# Main.net
KiCad netlist of a schematic drawn in Altium Designer
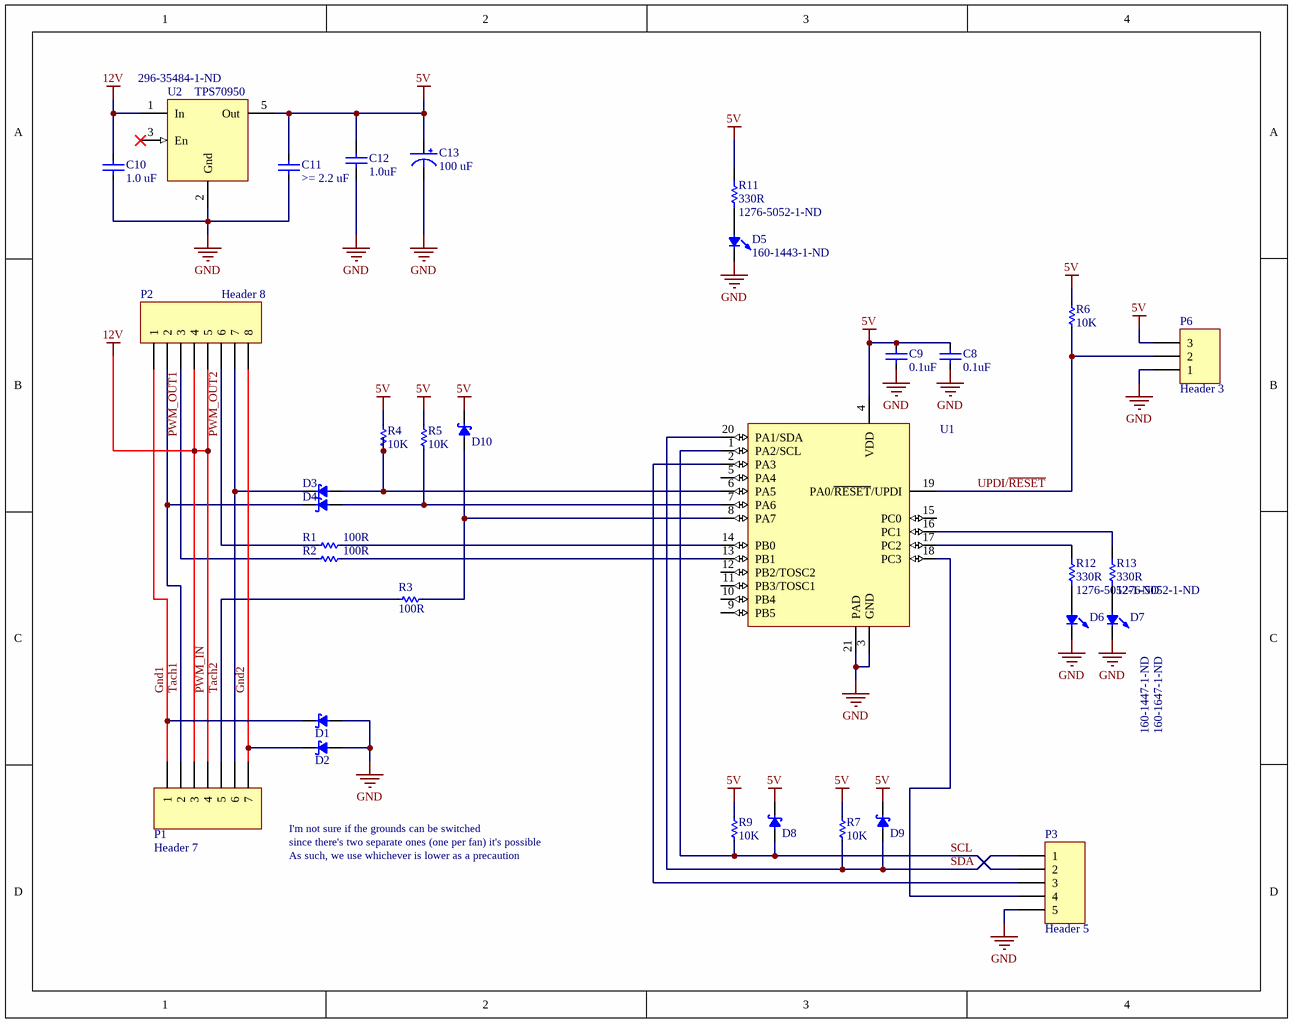
[diagram p0: Main.SchDoc]

(export (version "E")
  (design (tool "Eeschema 10.0.6"))
  (components
    (comp (ref "C8")
      (value "0.1uF")
      (footprint "0603C")
      (description "Capacitor")
      (fields (field (name "Comment") "Cap"))
      (libsource (lib "Miscellaneous Devices") (part "Cap"))
    )
    (comp (ref "C9")
      (value "0.1uF")
      (footprint "0603C")
      (description "Capacitor")
      (fields (field (name "Comment") "Cap"))
      (libsource (lib "Miscellaneous Devices") (part "Cap"))
    )
    (comp (ref "C10")
      (value "1.0 uF")
      (footprint "1206C")
      (description "Capacitor")
      (fields (field (name "Comment") "Cap") (field (name "PUBLISHER") "Altium Limited"))
      (libsource (lib "Miscellaneous Devices") (part "Cap"))
    )
    (comp (ref "C11")
      (value ">= 2.2 uF")
      (footprint "1206C")
      (description "Capacitor")
      (fields (field (name "Comment") "Cap") (field (name "PUBLISHER") "Altium Limited"))
      (libsource (lib "Miscellaneous Devices") (part "Cap"))
    )
    (comp (ref "C12")
      (value "1.0uF")
      (footprint "1206C")
      (description "Capacitor (Semiconductor SIM Model)")
      (fields (field (name "Comment") "Cap Semi") (field (name "PUBLISHER") "Altium Limited"))
      (libsource (lib "Miscellaneous Devices") (part "Cap Semi"))
    )
    (comp (ref "C13")
      (value "100 uF")
      (footprint "B")
      (libsource (lib "DAQ Sstem") (part "100 uf SMT Panasonic Cap"))
    )
    (comp (ref "D1")
      (value "Schottky Diode")
      (footprint "SOD-323")
      (libsource (lib "Unsorted") (part "Schottky Diode"))
    )
    (comp (ref "D2")
      (value "Schottky Diode")
      (footprint "SOD-323")
      (libsource (lib "Unsorted") (part "Schottky Diode"))
    )
    (comp (ref "D3")
      (value "Schottky Diode")
      (footprint "SOD-323")
      (libsource (lib "Unsorted") (part "Schottky Diode"))
    )
    (comp (ref "D4")
      (value "Schottky Diode")
      (footprint "SOD-323")
      (libsource (lib "Unsorted") (part "Schottky Diode"))
    )
    (comp (ref "D5")
      (value "LED0")
      (footprint "0603 SMT LED")
      (description "T 1 3/4 LED")
      (fields
        (field (name "SUPPLIER PART NUMBER 1") "160-1443-1-ND")
        (field (name "PUBLISHER") "Altium Limited")
      )
      (libsource (lib "Miscellaneous Devices") (part "LED0"))
    )
    (comp (ref "D6")
      (value "LED0")
      (footprint "0603 SMT LED")
      (description "T 1 3/4 LED")
      (fields
        (field (name "SUPPLIER PART NUMBER 1") "160-1447-1-ND")
        (field (name "PUBLISHER") "Altium Limited")
      )
      (libsource (lib "Miscellaneous Devices") (part "LED0"))
    )
    (comp (ref "D7")
      (value "LED0")
      (footprint "0603 SMT LED")
      (description "T 1 3/4 LED")
      (fields
        (field (name "SUPPLIER PART NUMBER 1") "160-1647-1-ND")
        (field (name "PUBLISHER") "Altium Limited")
      )
      (libsource (lib "Miscellaneous Devices") (part "LED0"))
    )
    (comp (ref "D8")
      (value "Schottky Diode")
      (footprint "SOD-323")
      (libsource (lib "Unsorted") (part "Schottky Diode"))
    )
    (comp (ref "D9")
      (value "Schottky Diode")
      (footprint "SOD-323")
      (libsource (lib "Unsorted") (part "Schottky Diode"))
    )
    (comp (ref "D10")
      (value "Schottky Diode")
      (footprint "SOD-323")
      (libsource (lib "Unsorted") (part "Schottky Diode"))
    )
    (comp (ref "P1")
      (value "Header 7")
      (footprint "HDR1X7")
      (description "Header, 7-Pin")
      (fields (field (name "PUBLISHER") "Altium Limited"))
      (libsource (lib "Miscellaneous Connectors") (part "Header 7"))
    )
    (comp (ref "P2")
      (value "Header 8")
      (footprint "HDR1X8")
      (description "Header, 8-Pin")
      (fields (field (name "PUBLISHER") "Altium Limited"))
      (libsource (lib "Miscellaneous Connectors") (part "Header 8"))
    )
    (comp (ref "P3")
      (value "Header 5")
      (footprint "Molex 5055670571")
      (description "Header, 5-Pin")
      (fields (field (name "PUBLISHER") "Altium Limited"))
      (libsource (lib "Miscellaneous Connectors") (part "Header 5"))
    )
    (comp (ref "P6")
      (value "Header 3")
      (footprint "HDR1X3")
      (description "Header, 3-Pin")
      (fields (field (name "PUBLISHER") "Altium Limited"))
      (libsource (lib "Miscellaneous Connectors") (part "Header 3"))
    )
    (comp (ref "R1")
      (value "100R")
      (footprint "0603R")
      (description "Semiconductor Resistor")
      (fields (field (name "Comment") "Res Semi Small") (field (name "PUBLISHER") "Altium Limited"))
      (libsource (lib "Miscellaneous Devices") (part "Res Semi Small"))
    )
    (comp (ref "R2")
      (value "100R")
      (footprint "0603R")
      (description "Semiconductor Resistor")
      (fields (field (name "Comment") "Res Semi Small") (field (name "PUBLISHER") "Altium Limited"))
      (libsource (lib "Miscellaneous Devices") (part "Res Semi Small"))
    )
    (comp (ref "R3")
      (value "100R")
      (footprint "0603R")
      (description "Semiconductor Resistor")
      (fields (field (name "Comment") "Res Semi Small") (field (name "PUBLISHER") "Altium Limited"))
      (libsource (lib "Miscellaneous Devices") (part "Res Semi Small"))
    )
    (comp (ref "R4")
      (value "10K")
      (footprint "0603R")
      (description "Semiconductor Resistor")
      (fields (field (name "Comment") "Res Semi Small") (field (name "PUBLISHER") "Altium Limited"))
      (libsource (lib "Miscellaneous Devices") (part "Res Semi Small"))
    )
    (comp (ref "R5")
      (value "10K")
      (footprint "0603R")
      (description "Semiconductor Resistor")
      (fields (field (name "Comment") "Res Semi Small") (field (name "PUBLISHER") "Altium Limited"))
      (libsource (lib "Miscellaneous Devices") (part "Res Semi Small"))
    )
    (comp (ref "R6")
      (value "10K")
      (footprint "0603R")
      (description "Semiconductor Resistor")
      (fields (field (name "Comment") "Res Semi Small") (field (name "PUBLISHER") "Altium Limited"))
      (libsource (lib "Miscellaneous Devices") (part "Res Semi Small"))
    )
    (comp (ref "R7")
      (value "10K")
      (footprint "0603R")
      (description "Semiconductor Resistor")
      (fields (field (name "Comment") "Res Semi Small") (field (name "PUBLISHER") "Altium Limited"))
      (libsource (lib "Miscellaneous Devices") (part "Res Semi Small"))
    )
    (comp (ref "R9")
      (value "10K")
      (footprint "0603R")
      (description "Semiconductor Resistor")
      (fields (field (name "Comment") "Res Semi Small") (field (name "PUBLISHER") "Altium Limited"))
      (libsource (lib "Miscellaneous Devices") (part "Res Semi Small"))
    )
    (comp (ref "R11")
      (value "330R")
      (footprint "0603R")
      (description "SMT Resistor")
      (fields
        (field (name "SUPPLIER PART NUMBER 1") "1276-5052-1-ND")
        (field (name "Comment") "Res Semi")
        (field (name "PUBLISHER") "Altium Limited")
      )
      (libsource (lib "Miscellaneous Devices") (part "Res Semi"))
    )
    (comp (ref "R12")
      (value "330R")
      (footprint "0603R")
      (description "SMT Resistor")
      (fields
        (field (name "SUPPLIER PART NUMBER 1") "1276-5052-1-ND")
        (field (name "Comment") "Res Semi")
        (field (name "PUBLISHER") "Altium Limited")
      )
      (libsource (lib "Miscellaneous Devices") (part "Res Semi"))
    )
    (comp (ref "R13")
      (value "330R")
      (footprint "0603R")
      (description "SMT Resistor")
      (fields
        (field (name "SUPPLIER PART NUMBER 1") "1276-5052-1-ND")
        (field (name "Comment") "Res Semi")
        (field (name "PUBLISHER") "Altium Limited")
      )
      (libsource (lib "Miscellaneous Devices") (part "Res Semi"))
    )
    (comp (ref "U1")
      (value "ATTiny1616-MFR")
      (footprint "QFN40P300X300X90_HS-21N")
      (libsource (lib "ICs") (part "ATTiny1616-MFR"))
    )
    (comp (ref "U2")
      (value "TPS70950")
      (footprint "SOT23-5AN")
      (description "150-mA, 30-V, Ultra-Low IQ, Wide Input Low-Dropout Regulator with Reverse Current Protection")
      (fields (field (name "SUPPLIER PART NUMBER 1") "296-35484-1-ND"))
      (libsource (lib "ICs") (part "TPS709XX"))
    )
  )
  (nets
    (net (code "1") (name "/Gnd1") (class "Default")
      (node (ref "D1") (pin "1") (pinfunction "1_1") (pintype "passive"))
      (node (ref "P1") (pin "1") (pinfunction "1_1") (pintype "passive"))
      (node (ref "P2") (pin "1") (pinfunction "1_1") (pintype "passive"))
    )
    (net (code "2") (name "/Gnd2") (class "Default")
      (node (ref "D2") (pin "1") (pinfunction "1_1") (pintype "passive"))
      (node (ref "P1") (pin "7") (pinfunction "7_7") (pintype "passive"))
      (node (ref "P2") (pin "8") (pinfunction "8_8") (pintype "passive"))
    )
    (net (code "3") (name "/PWM_OUT1") (class "Default")
      (node (ref "P2") (pin "3") (pinfunction "3_3") (pintype "passive"))
      (node (ref "R2") (pin "1") (pinfunction "1_1") (pintype "passive"))
    )
    (net (code "4") (name "/PWM_OUT2") (class "Default")
      (node (ref "P2") (pin "6") (pinfunction "6_6") (pintype "passive"))
      (node (ref "R1") (pin "1") (pinfunction "1_1") (pintype "passive"))
    )
    (net (code "5") (name "/SCL") (class "Default")
      (node (ref "D8") (pin "2") (pinfunction "2_2") (pintype "passive"))
      (node (ref "P3") (pin "2") (pinfunction "2_2") (pintype "passive"))
      (node (ref "R9") (pin "1") (pinfunction "1_1") (pintype "passive"))
      (node (ref "U1") (pin "1") (pinfunction "PA2/SCL_1") (pintype "bidirectional"))
    )
    (net (code "6") (name "/SDA") (class "Default")
      (node (ref "D9") (pin "2") (pinfunction "2_2") (pintype "passive"))
      (node (ref "P3") (pin "1") (pinfunction "1_1") (pintype "passive"))
      (node (ref "R7") (pin "1") (pinfunction "1_1") (pintype "passive"))
      (node (ref "U1") (pin "20") (pinfunction "PA1/SDA_20") (pintype "bidirectional"))
    )
    (net (code "7") (name "/Tach1") (class "Default")
      (node (ref "D4") (pin "1") (pinfunction "1_1") (pintype "passive"))
      (node (ref "P1") (pin "2") (pinfunction "2_2") (pintype "passive"))
      (node (ref "P2") (pin "2") (pinfunction "2_2") (pintype "passive"))
    )
    (net (code "8") (name "/Tach2") (class "Default")
      (node (ref "P1") (pin "5") (pinfunction "5_5") (pintype "passive"))
      (node (ref "R3") (pin "1") (pinfunction "1_1") (pintype "passive"))
    )
    (net (code "9") (name "/UPDI{slash}~{RESET}") (class "Default")
      (node (ref "P6") (pin "2") (pinfunction "2_2") (pintype "passive"))
      (node (ref "R6") (pin "1") (pinfunction "1_1") (pintype "passive"))
      (node (ref "U1") (pin "19") (pinfunction "PA0/~{RESET}/UPDI_19") (pintype "passive"))
    )
    (net (code "10") (name "5V") (class "Default")
      (node (ref "C11") (pin "2") (pinfunction "2_2") (pintype "passive"))
      (node (ref "C12") (pin "2") (pinfunction "2_2") (pintype "passive"))
      (node (ref "C13") (pin "1") (pinfunction "1_1") (pintype "passive"))
      (node (ref "C8") (pin "2") (pinfunction "2_2") (pintype "passive"))
      (node (ref "C9") (pin "2") (pinfunction "2_2") (pintype "passive"))
      (node (ref "D10") (pin "1") (pinfunction "1_1") (pintype "passive"))
      (node (ref "D8") (pin "1") (pinfunction "1_1") (pintype "passive"))
      (node (ref "D9") (pin "1") (pinfunction "1_1") (pintype "passive"))
      (node (ref "P6") (pin "3") (pinfunction "3_3") (pintype "passive"))
      (node (ref "R11") (pin "2") (pinfunction "2_2") (pintype "passive"))
      (node (ref "R4") (pin "2") (pinfunction "2_2") (pintype "passive"))
      (node (ref "R5") (pin "2") (pinfunction "2_2") (pintype "passive"))
      (node (ref "R6") (pin "2") (pinfunction "2_2") (pintype "passive"))
      (node (ref "R7") (pin "2") (pinfunction "2_2") (pintype "passive"))
      (node (ref "R9") (pin "2") (pinfunction "2_2") (pintype "passive"))
      (node (ref "U1") (pin "4") (pinfunction "VDD_4") (pintype "power_in"))
      (node (ref "U2") (pin "5") (pinfunction "Out_5") (pintype "power_in"))
    )
    (net (code "11") (name "12V") (class "Default")
      (node (ref "C10") (pin "2") (pinfunction "2_2") (pintype "passive"))
      (node (ref "P1") (pin "3") (pinfunction "3_3") (pintype "passive"))
      (node (ref "P1") (pin "4") (pinfunction "4_4") (pintype "passive"))
      (node (ref "P2") (pin "4") (pinfunction "4_4") (pintype "passive"))
      (node (ref "P2") (pin "5") (pinfunction "5_5") (pintype "passive"))
      (node (ref "U2") (pin "1") (pinfunction "In_1") (pintype "power_in"))
    )
    (net (code "12") (name "GND") (class "Default")
      (node (ref "C10") (pin "1") (pinfunction "1_1") (pintype "passive"))
      (node (ref "C11") (pin "1") (pinfunction "1_1") (pintype "passive"))
      (node (ref "C12") (pin "1") (pinfunction "1_1") (pintype "passive"))
      (node (ref "C13") (pin "2") (pinfunction "2_2") (pintype "passive"))
      (node (ref "C8") (pin "1") (pinfunction "1_1") (pintype "passive"))
      (node (ref "C9") (pin "1") (pinfunction "1_1") (pintype "passive"))
      (node (ref "D1") (pin "2") (pinfunction "2_2") (pintype "passive"))
      (node (ref "D2") (pin "2") (pinfunction "2_2") (pintype "passive"))
      (node (ref "D5") (pin "2") (pinfunction "2_2") (pintype "passive"))
      (node (ref "D6") (pin "2") (pinfunction "2_2") (pintype "passive"))
      (node (ref "D7") (pin "2") (pinfunction "2_2") (pintype "passive"))
      (node (ref "P3") (pin "5") (pinfunction "5_5") (pintype "passive"))
      (node (ref "P6") (pin "1") (pinfunction "1_1") (pintype "passive"))
      (node (ref "U1") (pin "21") (pinfunction "PAD_21") (pintype "power_in"))
      (node (ref "U1") (pin "3") (pinfunction "GND_3") (pintype "power_in"))
      (node (ref "U2") (pin "2") (pinfunction "Gnd_2") (pintype "power_in"))
    )
    (net (code "13") (name "Net-(D3-Pad1)") (class "Default")
      (node (ref "D3") (pin "1") (pinfunction "1_1") (pintype "passive"))
      (node (ref "P1") (pin "6") (pinfunction "6_6") (pintype "passive"))
      (node (ref "P2") (pin "7") (pinfunction "7_7") (pintype "passive"))
    )
    (net (code "14") (name "Net-(D5-Pad1)") (class "Default")
      (node (ref "D5") (pin "1") (pinfunction "1_1") (pintype "passive"))
      (node (ref "R11") (pin "1") (pinfunction "1_1") (pintype "passive"))
    )
    (net (code "15") (name "Net-(D6-Pad1)") (class "Default")
      (node (ref "D6") (pin "1") (pinfunction "1_1") (pintype "passive"))
      (node (ref "R12") (pin "1") (pinfunction "1_1") (pintype "passive"))
    )
    (net (code "16") (name "Net-(D7-Pad1)") (class "Default")
      (node (ref "D7") (pin "1") (pinfunction "1_1") (pintype "passive"))
      (node (ref "R13") (pin "1") (pinfunction "1_1") (pintype "passive"))
    )
    (net (code "17") (name "Net-(U1-PA3)") (class "Default")
      (node (ref "P3") (pin "3") (pinfunction "3_3") (pintype "passive"))
      (node (ref "U1") (pin "2") (pinfunction "PA3_2") (pintype "bidirectional"))
    )
    (net (code "18") (name "Net-(U1-PA5)") (class "Default")
      (node (ref "D3") (pin "2") (pinfunction "2_2") (pintype "passive"))
      (node (ref "R4") (pin "1") (pinfunction "1_1") (pintype "passive"))
      (node (ref "U1") (pin "6") (pinfunction "PA5_6") (pintype "bidirectional"))
    )
    (net (code "19") (name "Net-(U1-PA6)") (class "Default")
      (node (ref "D4") (pin "2") (pinfunction "2_2") (pintype "passive"))
      (node (ref "R5") (pin "1") (pinfunction "1_1") (pintype "passive"))
      (node (ref "U1") (pin "7") (pinfunction "PA6_7") (pintype "bidirectional"))
    )
    (net (code "20") (name "Net-(U1-PA7)") (class "Default")
      (node (ref "D10") (pin "2") (pinfunction "2_2") (pintype "passive"))
      (node (ref "R3") (pin "2") (pinfunction "2_2") (pintype "passive"))
      (node (ref "U1") (pin "8") (pinfunction "PA7_8") (pintype "bidirectional"))
    )
    (net (code "21") (name "Net-(U1-PB0)") (class "Default")
      (node (ref "R1") (pin "2") (pinfunction "2_2") (pintype "passive"))
      (node (ref "U1") (pin "14") (pinfunction "PB0_14") (pintype "bidirectional"))
    )
    (net (code "22") (name "Net-(U1-PB1)") (class "Default")
      (node (ref "R2") (pin "2") (pinfunction "2_2") (pintype "passive"))
      (node (ref "U1") (pin "13") (pinfunction "PB1_13") (pintype "bidirectional"))
    )
    (net (code "23") (name "Net-(U1-PC1)") (class "Default")
      (node (ref "R13") (pin "2") (pinfunction "2_2") (pintype "passive"))
      (node (ref "U1") (pin "16") (pinfunction "PC1_16") (pintype "bidirectional"))
    )
    (net (code "24") (name "Net-(U1-PC2)") (class "Default")
      (node (ref "R12") (pin "2") (pinfunction "2_2") (pintype "passive"))
      (node (ref "U1") (pin "17") (pinfunction "PC2_17") (pintype "bidirectional"))
    )
    (net (code "25") (name "Net-(U1-PC3)") (class "Default")
      (node (ref "P3") (pin "4") (pinfunction "4_4") (pintype "passive"))
      (node (ref "U1") (pin "18") (pinfunction "PC3_18") (pintype "bidirectional"))
    )
    (net (code "26") (name "unconnected-(U1-PA4-Pad5)") (class "Default")
      (node (ref "U1") (pin "5") (pinfunction "PA4_5") (pintype "bidirectional"))
    )
    (net (code "27") (name "unconnected-(U1-PB2{slash}TOSC2-Pad12)") (class "Default")
      (node (ref "U1") (pin "12") (pinfunction "PB2/TOSC2_12") (pintype "bidirectional"))
    )
    (net (code "28") (name "unconnected-(U1-PB3{slash}TOSC1-Pad11)") (class "Default")
      (node (ref "U1") (pin "11") (pinfunction "PB3/TOSC1_11") (pintype "bidirectional"))
    )
    (net (code "29") (name "unconnected-(U1-PB4-Pad10)") (class "Default")
      (node (ref "U1") (pin "10") (pinfunction "PB4_10") (pintype "bidirectional"))
    )
    (net (code "30") (name "unconnected-(U1-PB5-Pad9)") (class "Default")
      (node (ref "U1") (pin "9") (pinfunction "PB5_9") (pintype "bidirectional"))
    )
    (net (code "31") (name "unconnected-(U1-PC0-Pad15)") (class "Default")
      (node (ref "U1") (pin "15") (pinfunction "PC0_15") (pintype "bidirectional"))
    )
    (net (code "32") (name "unconnected-(U2-En-Pad3)") (class "Default")
      (node (ref "U2") (pin "3") (pinfunction "En_3") (pintype "input+no_connect"))
    )
  )
)
